# NMPavi280wires.net
KiCad netlist of a schematic drawn in EAGLE
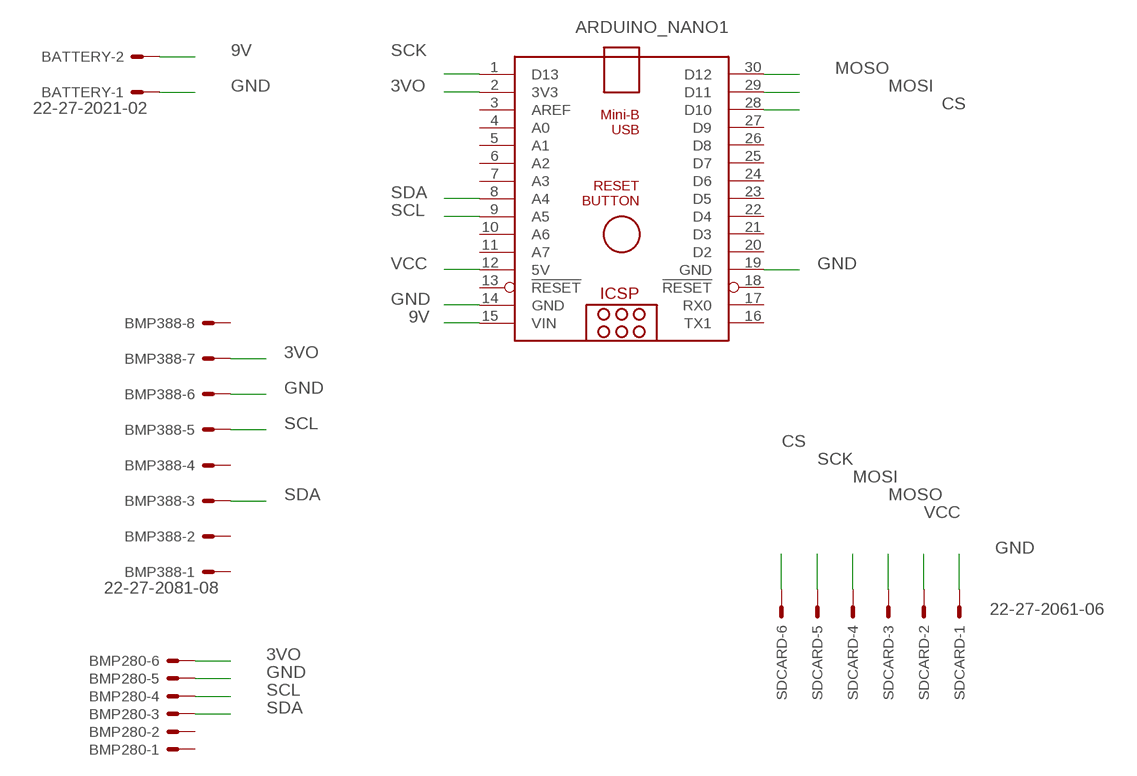
[diagram p0: schematic, sheet 1]

(export (version "E")
  (design (tool "Eeschema 10.0.6"))
  (components
    (comp (ref "ARDUINO_NANO1")
      (value "ARDUINO_NANO")
      (footprint "eagle-import:ARDUINO_NANO")
      (libsource (lib "eagle-import") (part "ARDUINO_NANO"))
    )
    (comp (ref "BATTERY")
      (value "22-27-2021-02")
      (footprint "eagle-import:6410-02")
      (fields (field (name "MF") "MOLEX"))
      (libsource (lib "eagle-import") (part "22-?-0227-2021"))
    )
    (comp (ref "BMP280")
      (value "22-23-2061")
      (footprint "eagle-import:22-23-2061")
      (fields (field (name "MF") "MOLEX"))
      (libsource (lib "eagle-import") (part "22-23-2061"))
    )
    (comp (ref "BMP388")
      (value "22-27-2081-08")
      (footprint "eagle-import:6410-08")
      (fields (field (name "MF") "MOLEX"))
      (libsource (lib "eagle-import") (part "22-?-0827-2081"))
    )
    (comp (ref "SDCARD")
      (value "22-27-2061-06")
      (footprint "eagle-import:6410-06")
      (fields (field (name "MF") "MOLEX"))
      (libsource (lib "eagle-import") (part "22-?-0627-2061"))
    )
  )
  (nets
    (net (code "1") (name "/3VO") (class "Default")
      (node (ref "ARDUINO_NANO1") (pin "2") (pinfunction "3V3_2") (pintype "output"))
      (node (ref "BMP280") (pin "6") (pinfunction "S_6") (pintype "passive"))
      (node (ref "BMP388") (pin "7") (pinfunction "S_7") (pintype "passive"))
    )
    (net (code "2") (name "/9V") (class "Default")
      (node (ref "ARDUINO_NANO1") (pin "15") (pinfunction "VIN_15") (pintype "power_in"))
      (node (ref "BATTERY") (pin "2") (pinfunction "S_2") (pintype "passive"))
    )
    (net (code "3") (name "/CS") (class "Default")
      (node (ref "ARDUINO_NANO1") (pin "28") (pinfunction "D10_28") (pintype "bidirectional"))
      (node (ref "SDCARD") (pin "6") (pinfunction "S_6") (pintype "passive"))
    )
    (net (code "4") (name "/GND") (class "Default")
      (node (ref "ARDUINO_NANO1") (pin "14") (pinfunction "GND_14") (pintype "power_in"))
      (node (ref "ARDUINO_NANO1") (pin "19") (pinfunction "GND_19") (pintype "power_in"))
      (node (ref "BATTERY") (pin "1") (pinfunction "S_1") (pintype "passive"))
      (node (ref "BMP280") (pin "5") (pinfunction "S_5") (pintype "passive"))
      (node (ref "BMP388") (pin "6") (pinfunction "S_6") (pintype "passive"))
      (node (ref "SDCARD") (pin "1") (pinfunction "S_1") (pintype "passive"))
    )
    (net (code "5") (name "/MOSI") (class "Default")
      (node (ref "ARDUINO_NANO1") (pin "29") (pinfunction "D11_29") (pintype "bidirectional"))
      (node (ref "SDCARD") (pin "4") (pinfunction "S_4") (pintype "passive"))
    )
    (net (code "6") (name "/MOSO") (class "Default")
      (node (ref "ARDUINO_NANO1") (pin "30") (pinfunction "D12_30") (pintype "bidirectional"))
      (node (ref "SDCARD") (pin "3") (pinfunction "S_3") (pintype "passive"))
    )
    (net (code "7") (name "/SCK") (class "Default")
      (node (ref "ARDUINO_NANO1") (pin "1") (pinfunction "D13_1") (pintype "bidirectional"))
      (node (ref "SDCARD") (pin "5") (pinfunction "S_5") (pintype "passive"))
    )
    (net (code "8") (name "/SCL") (class "Default")
      (node (ref "ARDUINO_NANO1") (pin "9") (pinfunction "A5_9") (pintype "bidirectional"))
      (node (ref "BMP280") (pin "4") (pinfunction "S_4") (pintype "passive"))
      (node (ref "BMP388") (pin "5") (pinfunction "S_5") (pintype "passive"))
    )
    (net (code "9") (name "/SDA") (class "Default")
      (node (ref "ARDUINO_NANO1") (pin "8") (pinfunction "A4_8") (pintype "bidirectional"))
      (node (ref "BMP280") (pin "3") (pinfunction "S_3") (pintype "passive"))
      (node (ref "BMP388") (pin "3") (pinfunction "S_3") (pintype "passive"))
    )
    (net (code "10") (name "/VCC") (class "Default")
      (node (ref "ARDUINO_NANO1") (pin "12") (pinfunction "5V_12") (pintype "power_in"))
      (node (ref "SDCARD") (pin "2") (pinfunction "S_2") (pintype "passive"))
    )
    (net (code "11") (name "unconnected-(ARDUINO_NANO1-A0-Pad4)") (class "Default")
      (node (ref "ARDUINO_NANO1") (pin "4") (pinfunction "A0_4") (pintype "bidirectional"))
    )
    (net (code "12") (name "unconnected-(ARDUINO_NANO1-A1-Pad5)") (class "Default")
      (node (ref "ARDUINO_NANO1") (pin "5") (pinfunction "A1_5") (pintype "bidirectional"))
    )
    (net (code "13") (name "unconnected-(ARDUINO_NANO1-A2-Pad6)") (class "Default")
      (node (ref "ARDUINO_NANO1") (pin "6") (pinfunction "A2_6") (pintype "bidirectional"))
    )
    (net (code "14") (name "unconnected-(ARDUINO_NANO1-A3-Pad7)") (class "Default")
      (node (ref "ARDUINO_NANO1") (pin "7") (pinfunction "A3_7") (pintype "bidirectional"))
    )
    (net (code "15") (name "unconnected-(ARDUINO_NANO1-A6-Pad10)") (class "Default")
      (node (ref "ARDUINO_NANO1") (pin "10") (pinfunction "A6_10") (pintype "bidirectional"))
    )
    (net (code "16") (name "unconnected-(ARDUINO_NANO1-A7-Pad11)") (class "Default")
      (node (ref "ARDUINO_NANO1") (pin "11") (pinfunction "A7_11") (pintype "bidirectional"))
    )
    (net (code "17") (name "unconnected-(ARDUINO_NANO1-AREF-Pad3)") (class "Default")
      (node (ref "ARDUINO_NANO1") (pin "3") (pinfunction "AREF_3") (pintype "input"))
    )
    (net (code "18") (name "unconnected-(ARDUINO_NANO1-D2-Pad20)") (class "Default")
      (node (ref "ARDUINO_NANO1") (pin "20") (pinfunction "D2_20") (pintype "bidirectional"))
    )
    (net (code "19") (name "unconnected-(ARDUINO_NANO1-D3-Pad21)") (class "Default")
      (node (ref "ARDUINO_NANO1") (pin "21") (pinfunction "D3_21") (pintype "bidirectional"))
    )
    (net (code "20") (name "unconnected-(ARDUINO_NANO1-D4-Pad22)") (class "Default")
      (node (ref "ARDUINO_NANO1") (pin "22") (pinfunction "D4_22") (pintype "bidirectional"))
    )
    (net (code "21") (name "unconnected-(ARDUINO_NANO1-D5-Pad23)") (class "Default")
      (node (ref "ARDUINO_NANO1") (pin "23") (pinfunction "D5_23") (pintype "bidirectional"))
    )
    (net (code "22") (name "unconnected-(ARDUINO_NANO1-D6-Pad24)") (class "Default")
      (node (ref "ARDUINO_NANO1") (pin "24") (pinfunction "D6_24") (pintype "bidirectional"))
    )
    (net (code "23") (name "unconnected-(ARDUINO_NANO1-D7-Pad25)") (class "Default")
      (node (ref "ARDUINO_NANO1") (pin "25") (pinfunction "D7_25") (pintype "bidirectional"))
    )
    (net (code "24") (name "unconnected-(ARDUINO_NANO1-D8-Pad26)") (class "Default")
      (node (ref "ARDUINO_NANO1") (pin "26") (pinfunction "D8_26") (pintype "bidirectional"))
    )
    (net (code "25") (name "unconnected-(ARDUINO_NANO1-D9-Pad27)") (class "Default")
      (node (ref "ARDUINO_NANO1") (pin "27") (pinfunction "D9_27") (pintype "bidirectional"))
    )
    (net (code "26") (name "unconnected-(ARDUINO_NANO1-RX0-Pad17)") (class "Default")
      (node (ref "ARDUINO_NANO1") (pin "17") (pinfunction "RX0_17") (pintype "bidirectional"))
    )
    (net (code "27") (name "unconnected-(ARDUINO_NANO1-TX1-Pad16)") (class "Default")
      (node (ref "ARDUINO_NANO1") (pin "16") (pinfunction "TX1_16") (pintype "bidirectional"))
    )
    (net (code "28") (name "unconnected-(ARDUINO_NANO1-~{RESET}-Pad13)") (class "Default")
      (node (ref "ARDUINO_NANO1") (pin "13") (pinfunction "~{RESET}_13") (pintype "input"))
    )
    (net (code "29") (name "unconnected-(ARDUINO_NANO1-~{RESET}-Pad18)") (class "Default")
      (node (ref "ARDUINO_NANO1") (pin "18") (pinfunction "~{RESET}_18") (pintype "input"))
    )
    (net (code "30") (name "unconnected-(BMP280A-S-Pad1)") (class "Default")
      (node (ref "BMP280") (pin "1") (pinfunction "S_1") (pintype "passive"))
    )
    (net (code "31") (name "unconnected-(BMP280B-S-Pad2)") (class "Default")
      (node (ref "BMP280") (pin "2") (pinfunction "S_2") (pintype "passive"))
    )
    (net (code "32") (name "unconnected-(BMP388A-S-Pad1)") (class "Default")
      (node (ref "BMP388") (pin "1") (pinfunction "S_1") (pintype "passive"))
    )
    (net (code "33") (name "unconnected-(BMP388B-S-Pad2)") (class "Default")
      (node (ref "BMP388") (pin "2") (pinfunction "S_2") (pintype "passive"))
    )
    (net (code "34") (name "unconnected-(BMP388D-S-Pad4)") (class "Default")
      (node (ref "BMP388") (pin "4") (pinfunction "S_4") (pintype "passive"))
    )
    (net (code "35") (name "unconnected-(BMP388H-S-Pad8)") (class "Default")
      (node (ref "BMP388") (pin "8") (pinfunction "S_8") (pintype "passive"))
    )
  )
)
